# Kopplingsschema.net
KiCad netlist of a schematic drawn in EAGLE
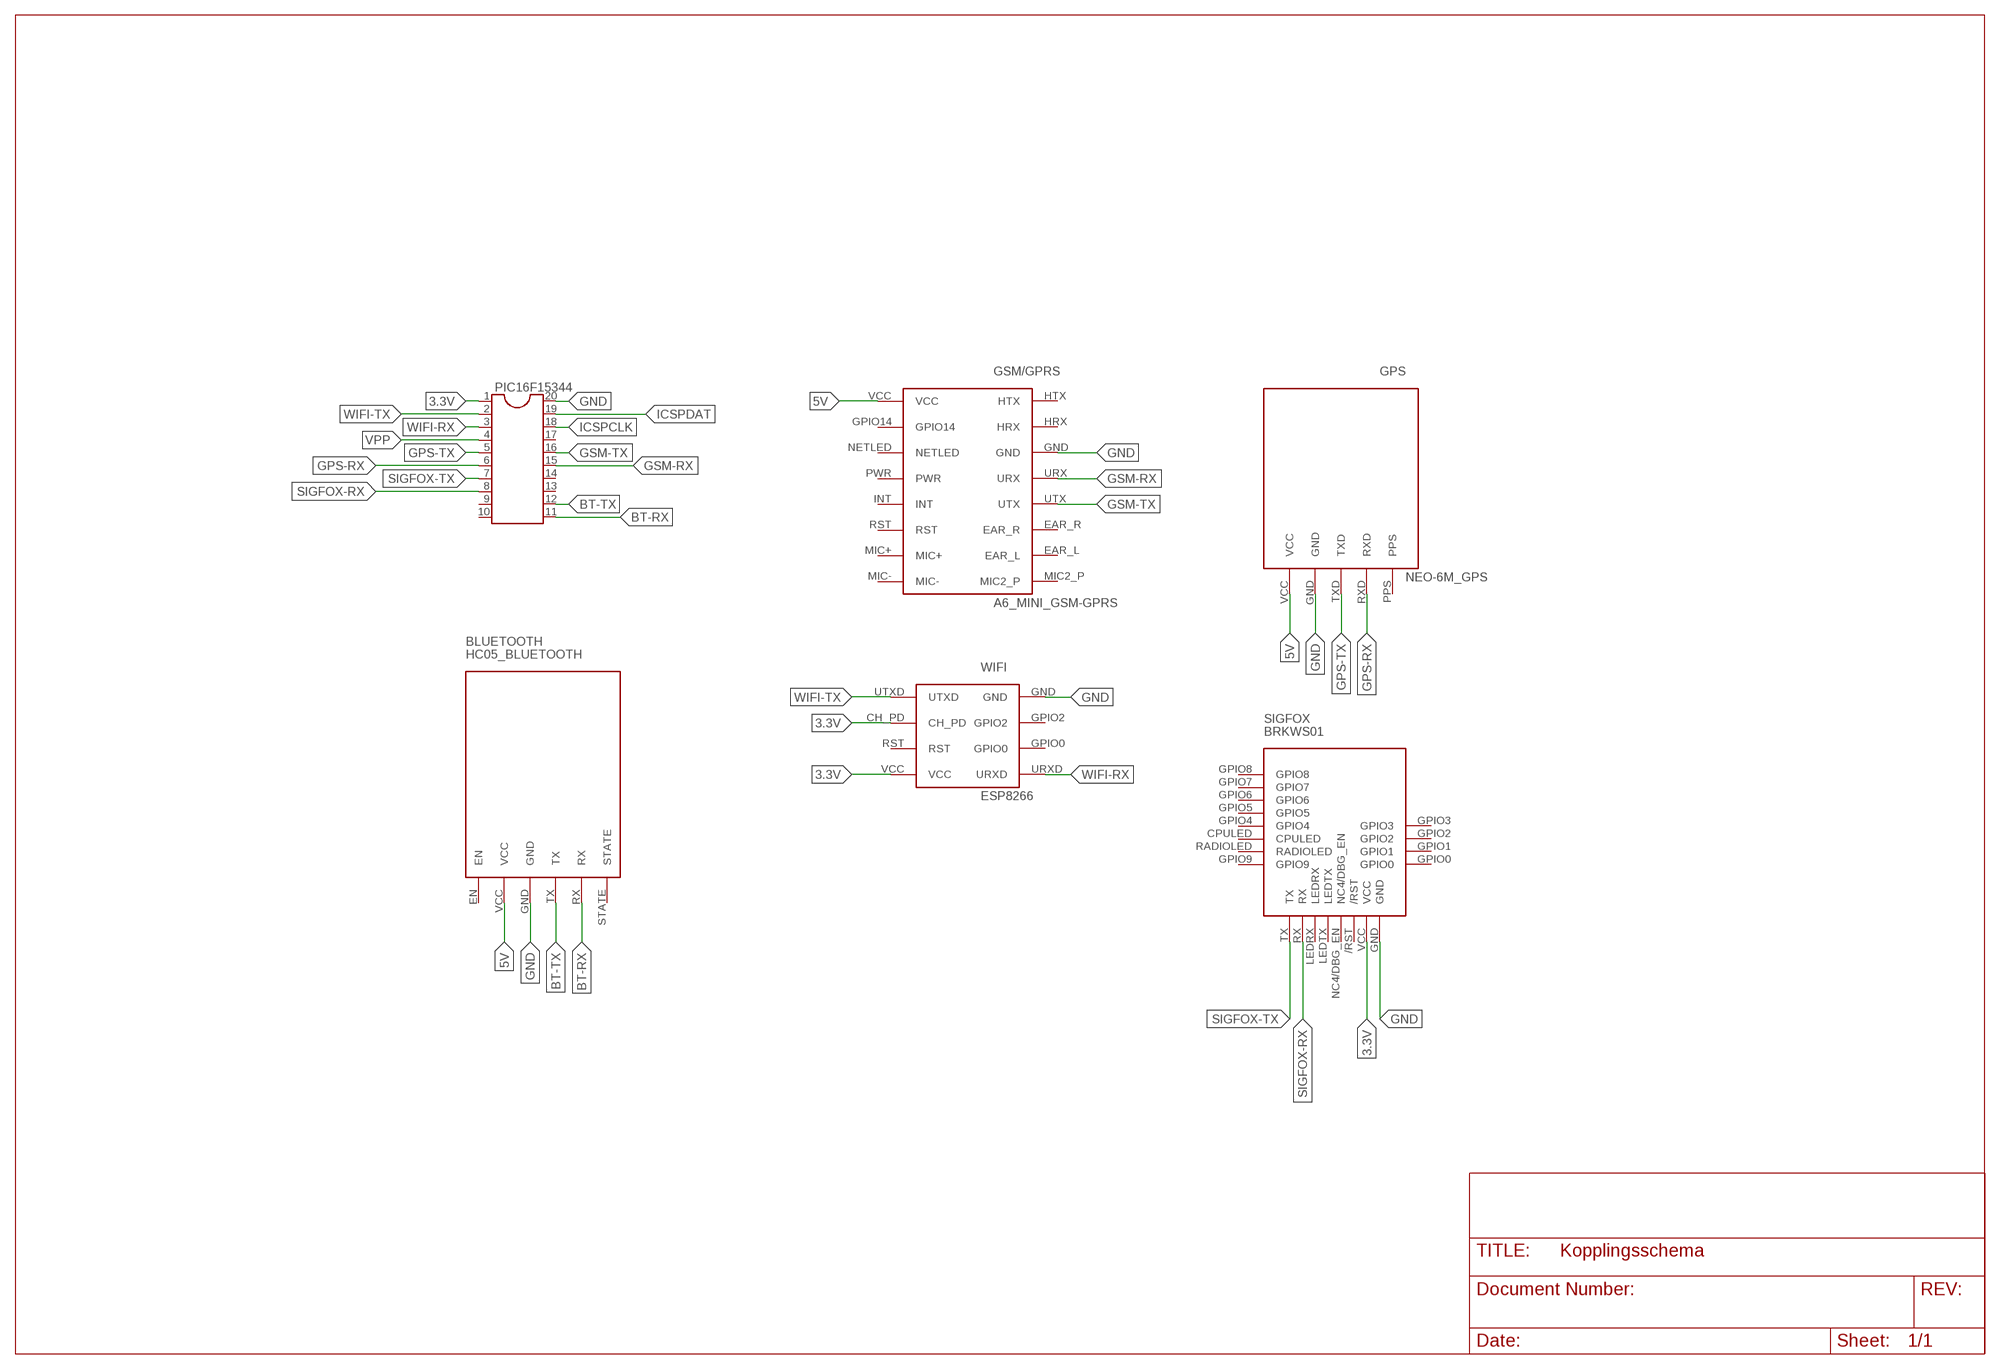
[diagram p0: schematic, sheet 1]

(export (version "E")
  (design (tool "Eeschema 10.0.6"))
  (components
    (comp (ref "BLUETOOTH")
      (value "HC05_BLUETOOTH")
      (footprint "eagle-import:HC05_BLUETOOTH")
      (libsource (lib "eagle-import") (part "HC05_BLUETOOTH"))
    )
    (comp (ref "GPS")
      (value "NEO-6M_GPS")
      (footprint "eagle-import:NEO-6M_GPS")
      (libsource (lib "eagle-import") (part "NEO-6M_GPS"))
    )
    (comp (ref "GSM/GPRS")
      (value "A6_MINI_GSM-GPRS")
      (footprint "eagle-import:A6_MINI_GSM-GPRS")
      (libsource (lib "eagle-import") (part "A6_MINI_GSM-GPRS"))
    )
    (comp (ref "PIC16F15344")
      (value "DIL20")
      (footprint "eagle-import:DIL20")
      (libsource (lib "eagle-import") (part "DIL20"))
    )
    (comp (ref "SIGFOX")
      (value "BRKWS01")
      (footprint "eagle-import:BRKWS01")
      (libsource (lib "eagle-import") (part "BRKWS01"))
    )
    (comp (ref "WIFI")
      (value "ESP8266")
      (footprint "eagle-import:ESP8266")
      (libsource (lib "eagle-import") (part "ESP8266"))
    )
  )
  (nets
    (net (code "1") (name "3.3V") (class "Default")
      (node (ref "PIC16F15344") (pin "1") (pinfunction "1_1") (pintype "passive"))
      (node (ref "SIGFOX") (pin "VCC") (pinfunction "VCC_VCC") (pintype "bidirectional"))
      (node (ref "WIFI") (pin "CH_PD") (pinfunction "CH_PD_CH_PD") (pintype "bidirectional"))
      (node (ref "WIFI") (pin "VCC") (pinfunction "VCC_VCC") (pintype "bidirectional"))
    )
    (net (code "2") (name "5V") (class "Default")
      (node (ref "BLUETOOTH") (pin "VCC") (pinfunction "VCC_VCC") (pintype "bidirectional"))
      (node (ref "GPS") (pin "VCC") (pinfunction "VCC_VCC") (pintype "bidirectional"))
      (node (ref "GSM/GPRS") (pin "VCC") (pinfunction "VCC_VCC") (pintype "bidirectional"))
    )
    (net (code "3") (name "BT-RX") (class "Default")
      (node (ref "BLUETOOTH") (pin "RX") (pinfunction "RX_RX") (pintype "bidirectional"))
      (node (ref "PIC16F15344") (pin "11") (pinfunction "11_11") (pintype "passive"))
    )
    (net (code "4") (name "BT-TX") (class "Default")
      (node (ref "BLUETOOTH") (pin "TX") (pinfunction "TX_TX") (pintype "bidirectional"))
      (node (ref "PIC16F15344") (pin "12") (pinfunction "12_12") (pintype "passive"))
    )
    (net (code "5") (name "GND") (class "Default")
      (node (ref "BLUETOOTH") (pin "GND") (pinfunction "GND_GND") (pintype "bidirectional"))
      (node (ref "GPS") (pin "GND") (pinfunction "GND_GND") (pintype "bidirectional"))
      (node (ref "GSM/GPRS") (pin "GND") (pinfunction "GND_GND") (pintype "bidirectional"))
      (node (ref "PIC16F15344") (pin "20") (pinfunction "20_20") (pintype "passive"))
      (node (ref "SIGFOX") (pin "GND") (pinfunction "GND_GND") (pintype "bidirectional"))
      (node (ref "WIFI") (pin "GND") (pinfunction "GND_GND") (pintype "bidirectional"))
    )
    (net (code "6") (name "GPS-RX") (class "Default")
      (node (ref "GPS") (pin "RXD") (pinfunction "RXD_RXD") (pintype "bidirectional"))
      (node (ref "PIC16F15344") (pin "6") (pinfunction "6_6") (pintype "passive"))
    )
    (net (code "7") (name "GPS-TX") (class "Default")
      (node (ref "GPS") (pin "TXD") (pinfunction "TXD_TXD") (pintype "bidirectional"))
      (node (ref "PIC16F15344") (pin "5") (pinfunction "5_5") (pintype "passive"))
    )
    (net (code "8") (name "GSM-RX") (class "Default")
      (node (ref "GSM/GPRS") (pin "URX") (pinfunction "URX_URX") (pintype "bidirectional"))
      (node (ref "PIC16F15344") (pin "15") (pinfunction "15_15") (pintype "passive"))
    )
    (net (code "9") (name "GSM-TX") (class "Default")
      (node (ref "GSM/GPRS") (pin "UTX") (pinfunction "UTX_UTX") (pintype "bidirectional"))
      (node (ref "PIC16F15344") (pin "16") (pinfunction "16_16") (pintype "passive"))
    )
    (net (code "10") (name "ICSPCLK") (class "Default")
      (node (ref "PIC16F15344") (pin "18") (pinfunction "18_18") (pintype "passive"))
    )
    (net (code "11") (name "ICSPDAT") (class "Default")
      (node (ref "PIC16F15344") (pin "19") (pinfunction "19_19") (pintype "passive"))
    )
    (net (code "12") (name "SIGFOX-RX") (class "Default")
      (node (ref "PIC16F15344") (pin "8") (pinfunction "8_8") (pintype "passive"))
      (node (ref "SIGFOX") (pin "RX") (pinfunction "RX_RX") (pintype "bidirectional"))
    )
    (net (code "13") (name "SIGFOX-TX") (class "Default")
      (node (ref "PIC16F15344") (pin "7") (pinfunction "7_7") (pintype "passive"))
      (node (ref "SIGFOX") (pin "TX") (pinfunction "TX_TX") (pintype "bidirectional"))
    )
    (net (code "14") (name "VPP") (class "Default")
      (node (ref "PIC16F15344") (pin "4") (pinfunction "4_4") (pintype "passive"))
    )
    (net (code "15") (name "WIFI-RX") (class "Default")
      (node (ref "PIC16F15344") (pin "3") (pinfunction "3_3") (pintype "passive"))
      (node (ref "WIFI") (pin "URXD") (pinfunction "URXD_URXD") (pintype "bidirectional"))
    )
    (net (code "16") (name "WIFI-TX") (class "Default")
      (node (ref "PIC16F15344") (pin "2") (pinfunction "2_2") (pintype "passive"))
      (node (ref "WIFI") (pin "UTXD") (pinfunction "UTXD_UTXD") (pintype "bidirectional"))
    )
    (net (code "17") (name "unconnected-(BLUETOOTH-PadEN)") (class "Default")
      (node (ref "BLUETOOTH") (pin "EN") (pinfunction "EN_EN") (pintype "bidirectional"))
    )
    (net (code "18") (name "unconnected-(BLUETOOTH-PadSTATE)") (class "Default")
      (node (ref "BLUETOOTH") (pin "STATE") (pinfunction "STATE_STATE") (pintype "bidirectional"))
    )
    (net (code "19") (name "unconnected-(GPS-PadPPS)") (class "Default")
      (node (ref "GPS") (pin "PPS") (pinfunction "PPS_PPS") (pintype "bidirectional"))
    )
    (net (code "20") (name "unconnected-(GSM/GPRS-PadEAR_L)") (class "Default")
      (node (ref "GSM/GPRS") (pin "EAR_L") (pinfunction "EAR_L_EAR_L") (pintype "bidirectional"))
    )
    (net (code "21") (name "unconnected-(GSM/GPRS-PadEAR_R)") (class "Default")
      (node (ref "GSM/GPRS") (pin "EAR_R") (pinfunction "EAR_R_EAR_R") (pintype "bidirectional"))
    )
    (net (code "22") (name "unconnected-(GSM/GPRS-PadGPIO14)") (class "Default")
      (node (ref "GSM/GPRS") (pin "GPIO14") (pinfunction "GPIO14_GPIO14") (pintype "bidirectional"))
    )
    (net (code "23") (name "unconnected-(GSM/GPRS-PadHRX)") (class "Default")
      (node (ref "GSM/GPRS") (pin "HRX") (pinfunction "HRX_HRX") (pintype "bidirectional"))
    )
    (net (code "24") (name "unconnected-(GSM/GPRS-PadHTX)") (class "Default")
      (node (ref "GSM/GPRS") (pin "HTX") (pinfunction "HTX_HTX") (pintype "bidirectional"))
    )
    (net (code "25") (name "unconnected-(GSM/GPRS-PadINT)") (class "Default")
      (node (ref "GSM/GPRS") (pin "INT") (pinfunction "INT_INT") (pintype "bidirectional"))
    )
    (net (code "26") (name "unconnected-(GSM/GPRS-PadMIC+)") (class "Default")
      (node (ref "GSM/GPRS") (pin "MIC+") (pinfunction "MIC+_MIC+") (pintype "bidirectional"))
    )
    (net (code "27") (name "unconnected-(GSM/GPRS-PadMIC-)") (class "Default")
      (node (ref "GSM/GPRS") (pin "MIC-") (pinfunction "MIC-_MIC-") (pintype "bidirectional"))
    )
    (net (code "28") (name "unconnected-(GSM/GPRS-PadMIC2_P)") (class "Default")
      (node (ref "GSM/GPRS") (pin "MIC2_P") (pinfunction "MIC2_P_MIC2_P") (pintype "bidirectional"))
    )
    (net (code "29") (name "unconnected-(GSM/GPRS-PadNETLED)") (class "Default")
      (node (ref "GSM/GPRS") (pin "NETLED") (pinfunction "NETLED_NETLED") (pintype "bidirectional"))
    )
    (net (code "30") (name "unconnected-(GSM/GPRS-PadPWR)") (class "Default")
      (node (ref "GSM/GPRS") (pin "PWR") (pinfunction "PWR_PWR") (pintype "bidirectional"))
    )
    (net (code "31") (name "unconnected-(GSM/GPRS-PadRST)") (class "Default")
      (node (ref "GSM/GPRS") (pin "RST") (pinfunction "RST_RST") (pintype "bidirectional"))
    )
    (net (code "32") (name "unconnected-(PIC16F15344-Pad9)") (class "Default")
      (node (ref "PIC16F15344") (pin "9") (pinfunction "9_9") (pintype "passive"))
    )
    (net (code "33") (name "unconnected-(PIC16F15344-Pad10)") (class "Default")
      (node (ref "PIC16F15344") (pin "10") (pinfunction "10_10") (pintype "passive"))
    )
    (net (code "34") (name "unconnected-(PIC16F15344-Pad13)") (class "Default")
      (node (ref "PIC16F15344") (pin "13") (pinfunction "13_13") (pintype "passive"))
    )
    (net (code "35") (name "unconnected-(PIC16F15344-Pad14)") (class "Default")
      (node (ref "PIC16F15344") (pin "14") (pinfunction "14_14") (pintype "passive"))
    )
    (net (code "36") (name "unconnected-(PIC16F15344-Pad17)") (class "Default")
      (node (ref "PIC16F15344") (pin "17") (pinfunction "17_17") (pintype "passive"))
    )
    (net (code "37") (name "unconnected-(SIGFOX-PadCPULED)") (class "Default")
      (node (ref "SIGFOX") (pin "CPULED") (pinfunction "CPULED_CPULED") (pintype "bidirectional"))
    )
    (net (code "38") (name "unconnected-(SIGFOX-PadGPIO0)") (class "Default")
      (node (ref "SIGFOX") (pin "GPIO0") (pinfunction "GPIO0_GPIO0") (pintype "bidirectional"))
    )
    (net (code "39") (name "unconnected-(SIGFOX-PadGPIO1)") (class "Default")
      (node (ref "SIGFOX") (pin "GPIO1") (pinfunction "GPIO1_GPIO1") (pintype "bidirectional"))
    )
    (net (code "40") (name "unconnected-(SIGFOX-PadGPIO2)") (class "Default")
      (node (ref "SIGFOX") (pin "GPIO2") (pinfunction "GPIO2_GPIO2") (pintype "bidirectional"))
    )
    (net (code "41") (name "unconnected-(SIGFOX-PadGPIO3)") (class "Default")
      (node (ref "SIGFOX") (pin "GPIO3") (pinfunction "GPIO3_GPIO3") (pintype "bidirectional"))
    )
    (net (code "42") (name "unconnected-(SIGFOX-PadGPIO4)") (class "Default")
      (node (ref "SIGFOX") (pin "GPIO4") (pinfunction "GPIO4_GPIO4") (pintype "bidirectional"))
    )
    (net (code "43") (name "unconnected-(SIGFOX-PadGPIO5)") (class "Default")
      (node (ref "SIGFOX") (pin "GPIO5") (pinfunction "GPIO5_GPIO5") (pintype "bidirectional"))
    )
    (net (code "44") (name "unconnected-(SIGFOX-PadGPIO6)") (class "Default")
      (node (ref "SIGFOX") (pin "GPIO6") (pinfunction "GPIO6_GPIO6") (pintype "bidirectional"))
    )
    (net (code "45") (name "unconnected-(SIGFOX-PadGPIO7)") (class "Default")
      (node (ref "SIGFOX") (pin "GPIO7") (pinfunction "GPIO7_GPIO7") (pintype "bidirectional"))
    )
    (net (code "46") (name "unconnected-(SIGFOX-PadGPIO8)") (class "Default")
      (node (ref "SIGFOX") (pin "GPIO8") (pinfunction "GPIO8_GPIO8") (pintype "bidirectional"))
    )
    (net (code "47") (name "unconnected-(SIGFOX-PadGPIO9)") (class "Default")
      (node (ref "SIGFOX") (pin "GPIO9") (pinfunction "GPIO9_GPIO9") (pintype "bidirectional"))
    )
    (net (code "48") (name "unconnected-(SIGFOX-PadLEDRX)") (class "Default")
      (node (ref "SIGFOX") (pin "LEDRX") (pinfunction "LEDRX_LEDRX") (pintype "bidirectional"))
    )
    (net (code "49") (name "unconnected-(SIGFOX-PadLEDTX)") (class "Default")
      (node (ref "SIGFOX") (pin "LEDTX") (pinfunction "LEDTX_LEDTX") (pintype "bidirectional"))
    )
    (net (code "50") (name "unconnected-(SIGFOX-PadNC4{slash}DBG_EN)") (class "Default")
      (node (ref "SIGFOX") (pin "NC4/DBG_EN") (pinfunction "NC4/DBG_EN_NC4/DBG_EN") (pintype "bidirectional"))
    )
    (net (code "51") (name "unconnected-(SIGFOX-PadRADIOLED)") (class "Default")
      (node (ref "SIGFOX") (pin "RADIOLED") (pinfunction "RADIOLED_RADIOLED") (pintype "bidirectional"))
    )
    (net (code "52") (name "unconnected-(SIGFOX-Pad{slash}RST)") (class "Default")
      (node (ref "SIGFOX") (pin "/RST") (pinfunction "/RST_/RST") (pintype "bidirectional"))
    )
    (net (code "53") (name "unconnected-(WIFI-PadGPIO0)") (class "Default")
      (node (ref "WIFI") (pin "GPIO0") (pinfunction "GPIO0_GPIO0") (pintype "bidirectional"))
    )
    (net (code "54") (name "unconnected-(WIFI-PadGPIO2)") (class "Default")
      (node (ref "WIFI") (pin "GPIO2") (pinfunction "GPIO2_GPIO2") (pintype "bidirectional"))
    )
    (net (code "55") (name "unconnected-(WIFI-PadRST)") (class "Default")
      (node (ref "WIFI") (pin "RST") (pinfunction "RST_RST") (pintype "bidirectional"))
    )
  )
)
